# DIOT_Connectors.net
KiCad netlist of a schematic drawn in Altium Designer
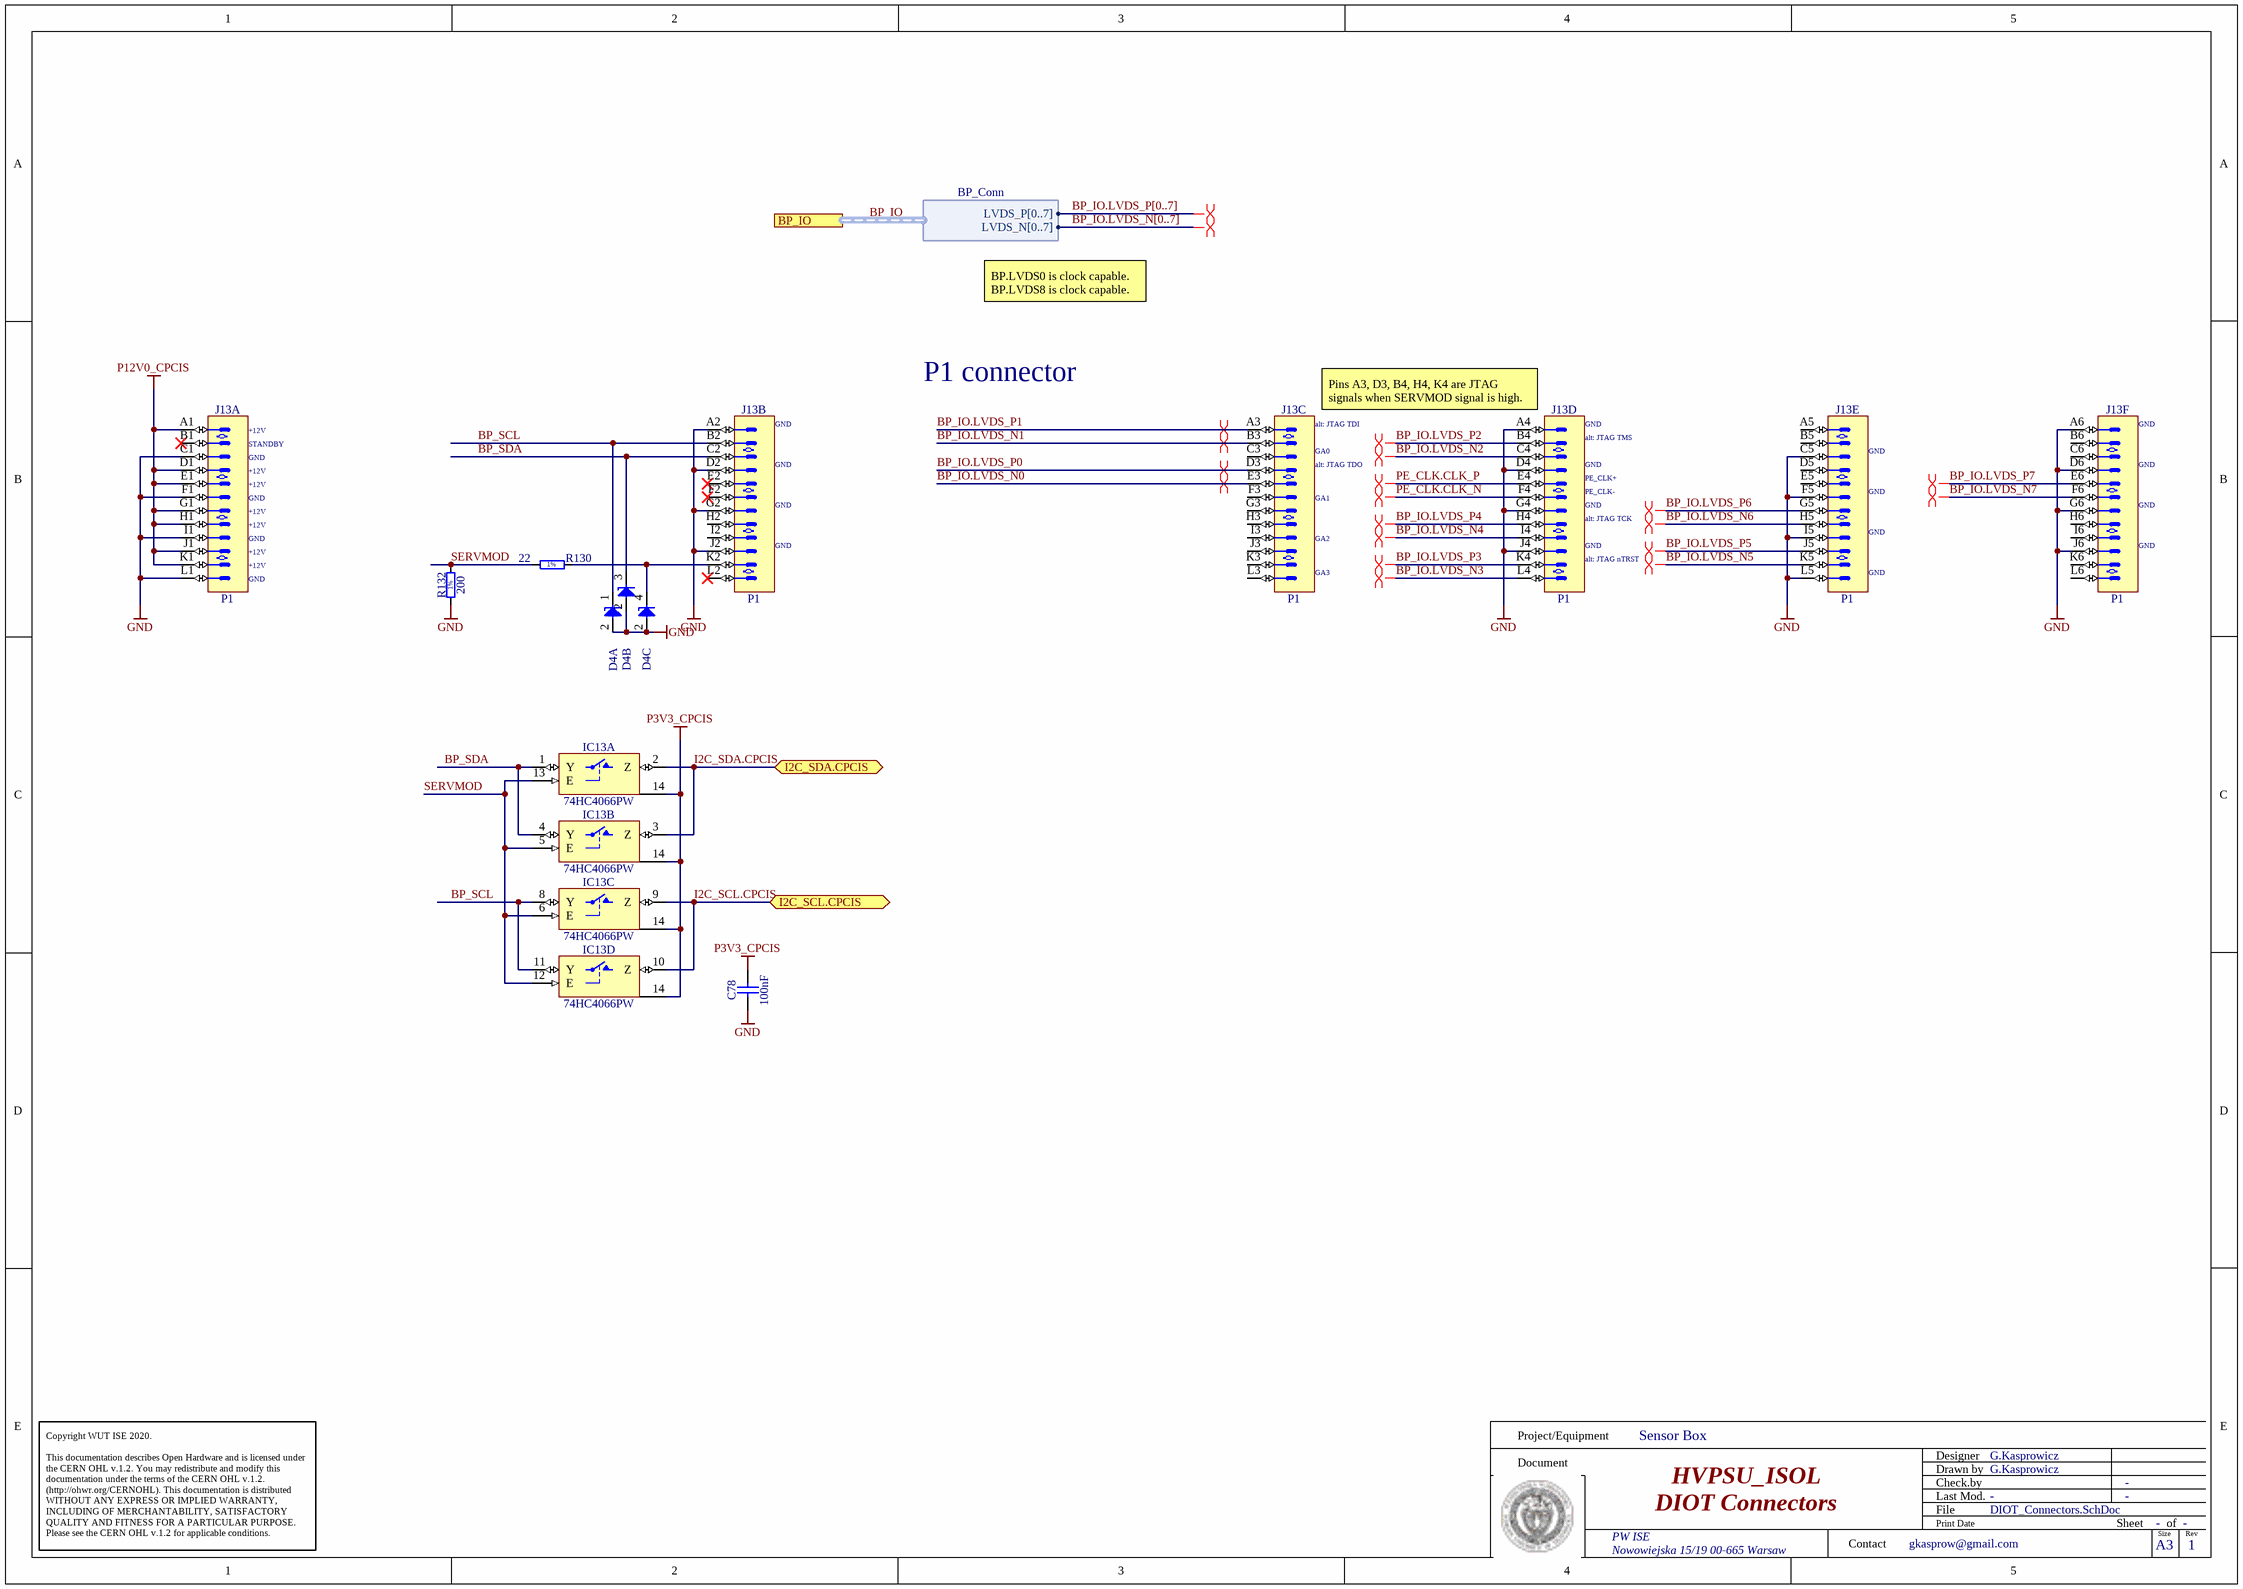
[diagram p0: DIOT_Connectors.SchDoc]

(export (version "E")
  (design (tool "Eeschema 10.0.6"))
  (components
    (comp (ref "C78")
      (value "100nF")
      (footprint "CAPC1005X55N")
      (description "Non-polarised capacitor")
      (fields
        (field (name "PART NUMBER") "CC0402_100NF_16V_10%_X5R")
        (field (name "VOLTAGE") "16V")
        (field (name "AUTHOR") "CERN DEM JLC")
      )
      (libsource (lib "Capacitors") (part "Capacitor - non polarized"))
    )
    (comp (ref "D4")
      (value "PESD3V3L5UY")
      (footprint "SOT65P210X110-6N")
      (description "Fivefold ESD Protection Diode Arrays")
      (fields
        (field (name "VOLTAGE") "3.3V")
        (field (name "POWER") "200W")
        (field (name "AUTHOR") "CERN DEM WB")
      )
      (libsource (lib "Modulator_pLib") (part "PESD3V3L5UY"))
    )
    (comp (ref "IC13")
      (value "74HC4066PW")
      (footprint "SOP65P640X110-14N")
      (fields (field (name "MANUFACTURER") "NXP SEMICONDUCTORS") (field (name "AUTHOR") "CERN DEM JLC"))
      (libsource (lib "ICs And Semiconductors") (part "4066"))
    )
    (comp (ref "J13")
      (value "P1")
      (footprint "AMPHENOL_10052825-101LF")
      (description "72 Contacts Header, 6 Columns, 4 Pairs per Column")
      (fields
        (field (name "PART NUMBER") "AMPHENOL_10052825-101LF")
        (field (name "MANUFACTURER") "AMPHENOL")
        (field (name "AUTHOR") "CERN DEM MR")
      )
      (libsource (lib "Connectors") (part "AMPHENOL_10052825-101LF"))
    )
    (comp (ref "R130")
      (value "22")
      (footprint "RESC1005X40N")
      (description "Resistor - 1%")
      (fields
        (field (name "PART NUMBER") "R0402_22R_1%_0.0625W_100PPM")
        (field (name "POWER") "0.0625W")
        (field (name "AUTHOR") "CERN DEM JLC")
      )
      (libsource (lib "Resistors") (part "Resistor - 1%"))
    )
    (comp (ref "R132")
      (value "200")
      (footprint "RESC1005X40N")
      (description "Resistor - 1%")
      (fields
        (field (name "PART NUMBER") "R0402_200R_1%_0.0625W_100PPM")
        (field (name "POWER") "0.0625W")
        (field (name "AUTHOR") "CERN DEM JLC")
      )
      (libsource (lib "Resistors") (part "Resistor - 1%"))
    )
  )
  (nets
    (net (code "2") (name "/BP_IO.LVDS_N0") (class "Default")
      (node (ref "J13") (pin "E3") (pinfunction "E3_E3") (pintype "bidirectional"))
    )
    (net (code "3") (name "/BP_IO.LVDS_N1") (class "Default")
      (node (ref "J13") (pin "B3") (pinfunction "B3_B3") (pintype "bidirectional"))
    )
    (net (code "4") (name "/BP_IO.LVDS_N2") (class "Default")
      (node (ref "J13") (pin "C4") (pinfunction "C4_C4") (pintype "bidirectional"))
    )
    (net (code "5") (name "/BP_IO.LVDS_N3") (class "Default")
      (node (ref "J13") (pin "L4") (pinfunction "L4_L4") (pintype "bidirectional"))
    )
    (net (code "6") (name "/BP_IO.LVDS_N4") (class "Default")
      (node (ref "J13") (pin "I4") (pinfunction "I4_I4") (pintype "bidirectional"))
    )
    (net (code "7") (name "/BP_IO.LVDS_N5") (class "Default")
      (node (ref "J13") (pin "K5") (pinfunction "K5_K5") (pintype "bidirectional"))
    )
    (net (code "8") (name "/BP_IO.LVDS_N6") (class "Default")
      (node (ref "J13") (pin "H5") (pinfunction "H5_H5") (pintype "bidirectional"))
    )
    (net (code "9") (name "/BP_IO.LVDS_N7") (class "Default")
      (node (ref "J13") (pin "F6") (pinfunction "F6_F6") (pintype "bidirectional"))
    )
    (net (code "11") (name "/BP_IO.LVDS_P0") (class "Default")
      (node (ref "J13") (pin "D3") (pinfunction "D3_D3") (pintype "bidirectional"))
    )
    (net (code "12") (name "/BP_IO.LVDS_P1") (class "Default")
      (node (ref "J13") (pin "A3") (pinfunction "A3_A3") (pintype "bidirectional"))
    )
    (net (code "13") (name "/BP_IO.LVDS_P2") (class "Default")
      (node (ref "J13") (pin "B4") (pinfunction "B4_B4") (pintype "bidirectional"))
    )
    (net (code "14") (name "/BP_IO.LVDS_P3") (class "Default")
      (node (ref "J13") (pin "K4") (pinfunction "K4_K4") (pintype "bidirectional"))
    )
    (net (code "15") (name "/BP_IO.LVDS_P4") (class "Default")
      (node (ref "J13") (pin "H4") (pinfunction "H4_H4") (pintype "bidirectional"))
    )
    (net (code "16") (name "/BP_IO.LVDS_P5") (class "Default")
      (node (ref "J13") (pin "J5") (pinfunction "J5_J5") (pintype "bidirectional"))
    )
    (net (code "17") (name "/BP_IO.LVDS_P6") (class "Default")
      (node (ref "J13") (pin "G5") (pinfunction "G5_G5") (pintype "bidirectional"))
    )
    (net (code "18") (name "/BP_IO.LVDS_P7") (class "Default")
      (node (ref "J13") (pin "E6") (pinfunction "E6_E6") (pintype "bidirectional"))
    )
    (net (code "21") (name "/BP_SCL") (class "Default")
      (node (ref "D4") (pin "1") (pinfunction "C_1") (pintype "passive"))
      (node (ref "IC13") (pin "11") (pinfunction "Y_11") (pintype "bidirectional"))
      (node (ref "IC13") (pin "8") (pinfunction "Y_8") (pintype "bidirectional"))
      (node (ref "J13") (pin "B2") (pinfunction "B2_B2") (pintype "bidirectional"))
    )
    (net (code "22") (name "/BP_SDA") (class "Default")
      (node (ref "D4") (pin "3") (pinfunction "C_3") (pintype "passive"))
      (node (ref "IC13") (pin "1") (pinfunction "Y_1") (pintype "bidirectional"))
      (node (ref "IC13") (pin "4") (pinfunction "Y_4") (pintype "bidirectional"))
      (node (ref "J13") (pin "C2") (pinfunction "C2_C2") (pintype "bidirectional"))
    )
    (net (code "23") (name "/I2C_SCL.CPCIS") (class "Default")
      (node (ref "IC13") (pin "10") (pinfunction "Z_10") (pintype "bidirectional"))
      (node (ref "IC13") (pin "9") (pinfunction "Z_9") (pintype "bidirectional"))
    )
    (net (code "24") (name "/I2C_SDA.CPCIS") (class "Default")
      (node (ref "IC13") (pin "2") (pinfunction "Z_2") (pintype "bidirectional"))
      (node (ref "IC13") (pin "3") (pinfunction "Z_3") (pintype "bidirectional"))
    )
    (net (code "25") (name "/PE_CLK.CLK_N") (class "Default")
      (node (ref "J13") (pin "F4") (pinfunction "F4_F4") (pintype "bidirectional"))
    )
    (net (code "26") (name "/PE_CLK.CLK_P") (class "Default")
      (node (ref "J13") (pin "E4") (pinfunction "E4_E4") (pintype "bidirectional"))
    )
    (net (code "27") (name "/SERVMOD") (class "Default")
      (node (ref "IC13") (pin "12") (pinfunction "E_12") (pintype "input"))
      (node (ref "IC13") (pin "13") (pinfunction "E_13") (pintype "input"))
      (node (ref "IC13") (pin "5") (pinfunction "E_5") (pintype "input"))
      (node (ref "IC13") (pin "6") (pinfunction "E_6") (pintype "input"))
      (node (ref "R130") (pin "1") (pinfunction "1_1") (pintype "passive"))
      (node (ref "R132") (pin "2") (pinfunction "2_2") (pintype "passive"))
    )
    (net (code "28") (name "GND") (class "Default")
      (node (ref "C78") (pin "1") (pinfunction "1_1") (pintype "passive"))
      (node (ref "D4") (pin "2") (pinfunction "A_2") (pintype "passive"))
      (node (ref "IC13") (pin "7") (pinfunction "GND_7") (pintype "power_in"))
      (node (ref "J13") (pin "A2") (pinfunction "A2_A2") (pintype "bidirectional"))
      (node (ref "J13") (pin "A4") (pinfunction "A4_A4") (pintype "bidirectional"))
      (node (ref "J13") (pin "A6") (pinfunction "A6_A6") (pintype "bidirectional"))
      (node (ref "J13") (pin "C1") (pinfunction "C1_C1") (pintype "bidirectional"))
      (node (ref "J13") (pin "C5") (pinfunction "C5_C5") (pintype "bidirectional"))
      (node (ref "J13") (pin "D2") (pinfunction "D2_D2") (pintype "bidirectional"))
      (node (ref "J13") (pin "D4") (pinfunction "D4_D4") (pintype "bidirectional"))
      (node (ref "J13") (pin "D6") (pinfunction "D6_D6") (pintype "bidirectional"))
      (node (ref "J13") (pin "F1") (pinfunction "F1_F1") (pintype "bidirectional"))
      (node (ref "J13") (pin "F5") (pinfunction "F5_F5") (pintype "bidirectional"))
      (node (ref "J13") (pin "G2") (pinfunction "G2_G2") (pintype "bidirectional"))
      (node (ref "J13") (pin "G4") (pinfunction "G4_G4") (pintype "bidirectional"))
      (node (ref "J13") (pin "G6") (pinfunction "G6_G6") (pintype "bidirectional"))
      (node (ref "J13") (pin "I1") (pinfunction "I1_I1") (pintype "bidirectional"))
      (node (ref "J13") (pin "I5") (pinfunction "I5_I5") (pintype "bidirectional"))
      (node (ref "J13") (pin "J2") (pinfunction "J2_J2") (pintype "bidirectional"))
      (node (ref "J13") (pin "J4") (pinfunction "J4_J4") (pintype "bidirectional"))
      (node (ref "J13") (pin "J6") (pinfunction "J6_J6") (pintype "bidirectional"))
      (node (ref "J13") (pin "L1") (pinfunction "L1_L1") (pintype "bidirectional"))
      (node (ref "J13") (pin "L5") (pinfunction "L5_L5") (pintype "bidirectional"))
      (node (ref "R132") (pin "1") (pinfunction "1_1") (pintype "passive"))
    )
    (net (code "29") (name "Net-(D4C-C)") (class "Default")
      (node (ref "D4") (pin "4") (pinfunction "C_4") (pintype "passive"))
      (node (ref "J13") (pin "K2") (pinfunction "K2_K2") (pintype "bidirectional"))
      (node (ref "R130") (pin "2") (pinfunction "2_2") (pintype "passive"))
    )
    (net (code "30") (name "P3V3_CPCIS") (class "Default")
      (node (ref "C78") (pin "2") (pinfunction "2_2") (pintype "passive"))
      (node (ref "IC13") (pin "14") (pinfunction "VCC_14") (pintype "power_in"))
    )
    (net (code "31") (name "P12V0_CPCIS") (class "Default")
      (node (ref "J13") (pin "A1") (pinfunction "A1_A1") (pintype "bidirectional"))
      (node (ref "J13") (pin "D1") (pinfunction "D1_D1") (pintype "bidirectional"))
      (node (ref "J13") (pin "E1") (pinfunction "E1_E1") (pintype "bidirectional"))
      (node (ref "J13") (pin "G1") (pinfunction "G1_G1") (pintype "bidirectional"))
      (node (ref "J13") (pin "H1") (pinfunction "H1_H1") (pintype "bidirectional"))
      (node (ref "J13") (pin "J1") (pinfunction "J1_J1") (pintype "bidirectional"))
      (node (ref "J13") (pin "K1") (pinfunction "K1_K1") (pintype "bidirectional"))
    )
    (net (code "32") (name "unconnected-(J13-PadA5)") (class "Default")
      (node (ref "J13") (pin "A5") (pinfunction "A5_A5") (pintype "bidirectional"))
    )
    (net (code "33") (name "unconnected-(J13-PadB1)") (class "Default")
      (node (ref "J13") (pin "B1") (pinfunction "B1_B1") (pintype "bidirectional+no_connect"))
    )
    (net (code "34") (name "unconnected-(J13-PadB5)") (class "Default")
      (node (ref "J13") (pin "B5") (pinfunction "B5_B5") (pintype "bidirectional"))
    )
    (net (code "35") (name "unconnected-(J13-PadB6)") (class "Default")
      (node (ref "J13") (pin "B6") (pinfunction "B6_B6") (pintype "bidirectional"))
    )
    (net (code "36") (name "unconnected-(J13-PadC3)") (class "Default")
      (node (ref "J13") (pin "C3") (pinfunction "C3_C3") (pintype "bidirectional"))
    )
    (net (code "37") (name "unconnected-(J13-PadC6)") (class "Default")
      (node (ref "J13") (pin "C6") (pinfunction "C6_C6") (pintype "bidirectional"))
    )
    (net (code "38") (name "unconnected-(J13-PadD5)") (class "Default")
      (node (ref "J13") (pin "D5") (pinfunction "D5_D5") (pintype "bidirectional"))
    )
    (net (code "39") (name "unconnected-(J13-PadE2)") (class "Default")
      (node (ref "J13") (pin "E2") (pinfunction "E2_E2") (pintype "bidirectional+no_connect"))
    )
    (net (code "40") (name "unconnected-(J13-PadE5)") (class "Default")
      (node (ref "J13") (pin "E5") (pinfunction "E5_E5") (pintype "bidirectional"))
    )
    (net (code "41") (name "unconnected-(J13-PadF2)") (class "Default")
      (node (ref "J13") (pin "F2") (pinfunction "F2_F2") (pintype "bidirectional+no_connect"))
    )
    (net (code "42") (name "unconnected-(J13-PadF3)") (class "Default")
      (node (ref "J13") (pin "F3") (pinfunction "F3_F3") (pintype "bidirectional"))
    )
    (net (code "43") (name "unconnected-(J13-PadG3)") (class "Default")
      (node (ref "J13") (pin "G3") (pinfunction "G3_G3") (pintype "bidirectional"))
    )
    (net (code "44") (name "unconnected-(J13-PadH2)") (class "Default")
      (node (ref "J13") (pin "H2") (pinfunction "H2_H2") (pintype "bidirectional"))
    )
    (net (code "45") (name "unconnected-(J13-PadH3)") (class "Default")
      (node (ref "J13") (pin "H3") (pinfunction "H3_H3") (pintype "bidirectional"))
    )
    (net (code "46") (name "unconnected-(J13-PadH6)") (class "Default")
      (node (ref "J13") (pin "H6") (pinfunction "H6_H6") (pintype "bidirectional"))
    )
    (net (code "47") (name "unconnected-(J13-PadI2)") (class "Default")
      (node (ref "J13") (pin "I2") (pinfunction "I2_I2") (pintype "bidirectional"))
    )
    (net (code "48") (name "unconnected-(J13-PadI3)") (class "Default")
      (node (ref "J13") (pin "I3") (pinfunction "I3_I3") (pintype "bidirectional"))
    )
    (net (code "49") (name "unconnected-(J13-PadI6)") (class "Default")
      (node (ref "J13") (pin "I6") (pinfunction "I6_I6") (pintype "bidirectional"))
    )
    (net (code "50") (name "unconnected-(J13-PadJ3)") (class "Default")
      (node (ref "J13") (pin "J3") (pinfunction "J3_J3") (pintype "bidirectional"))
    )
    (net (code "51") (name "unconnected-(J13-PadK3)") (class "Default")
      (node (ref "J13") (pin "K3") (pinfunction "K3_K3") (pintype "bidirectional"))
    )
    (net (code "52") (name "unconnected-(J13-PadK6)") (class "Default")
      (node (ref "J13") (pin "K6") (pinfunction "K6_K6") (pintype "bidirectional"))
    )
    (net (code "53") (name "unconnected-(J13-PadL2)") (class "Default")
      (node (ref "J13") (pin "L2") (pinfunction "L2_L2") (pintype "bidirectional+no_connect"))
    )
    (net (code "54") (name "unconnected-(J13-PadL3)") (class "Default")
      (node (ref "J13") (pin "L3") (pinfunction "L3_L3") (pintype "bidirectional"))
    )
    (net (code "55") (name "unconnected-(J13-PadL6)") (class "Default")
      (node (ref "J13") (pin "L6") (pinfunction "L6_L6") (pintype "bidirectional"))
    )
  )
)
